# Adafruit_RS232_Pal.net
KiCad netlist of a schematic drawn in EAGLE
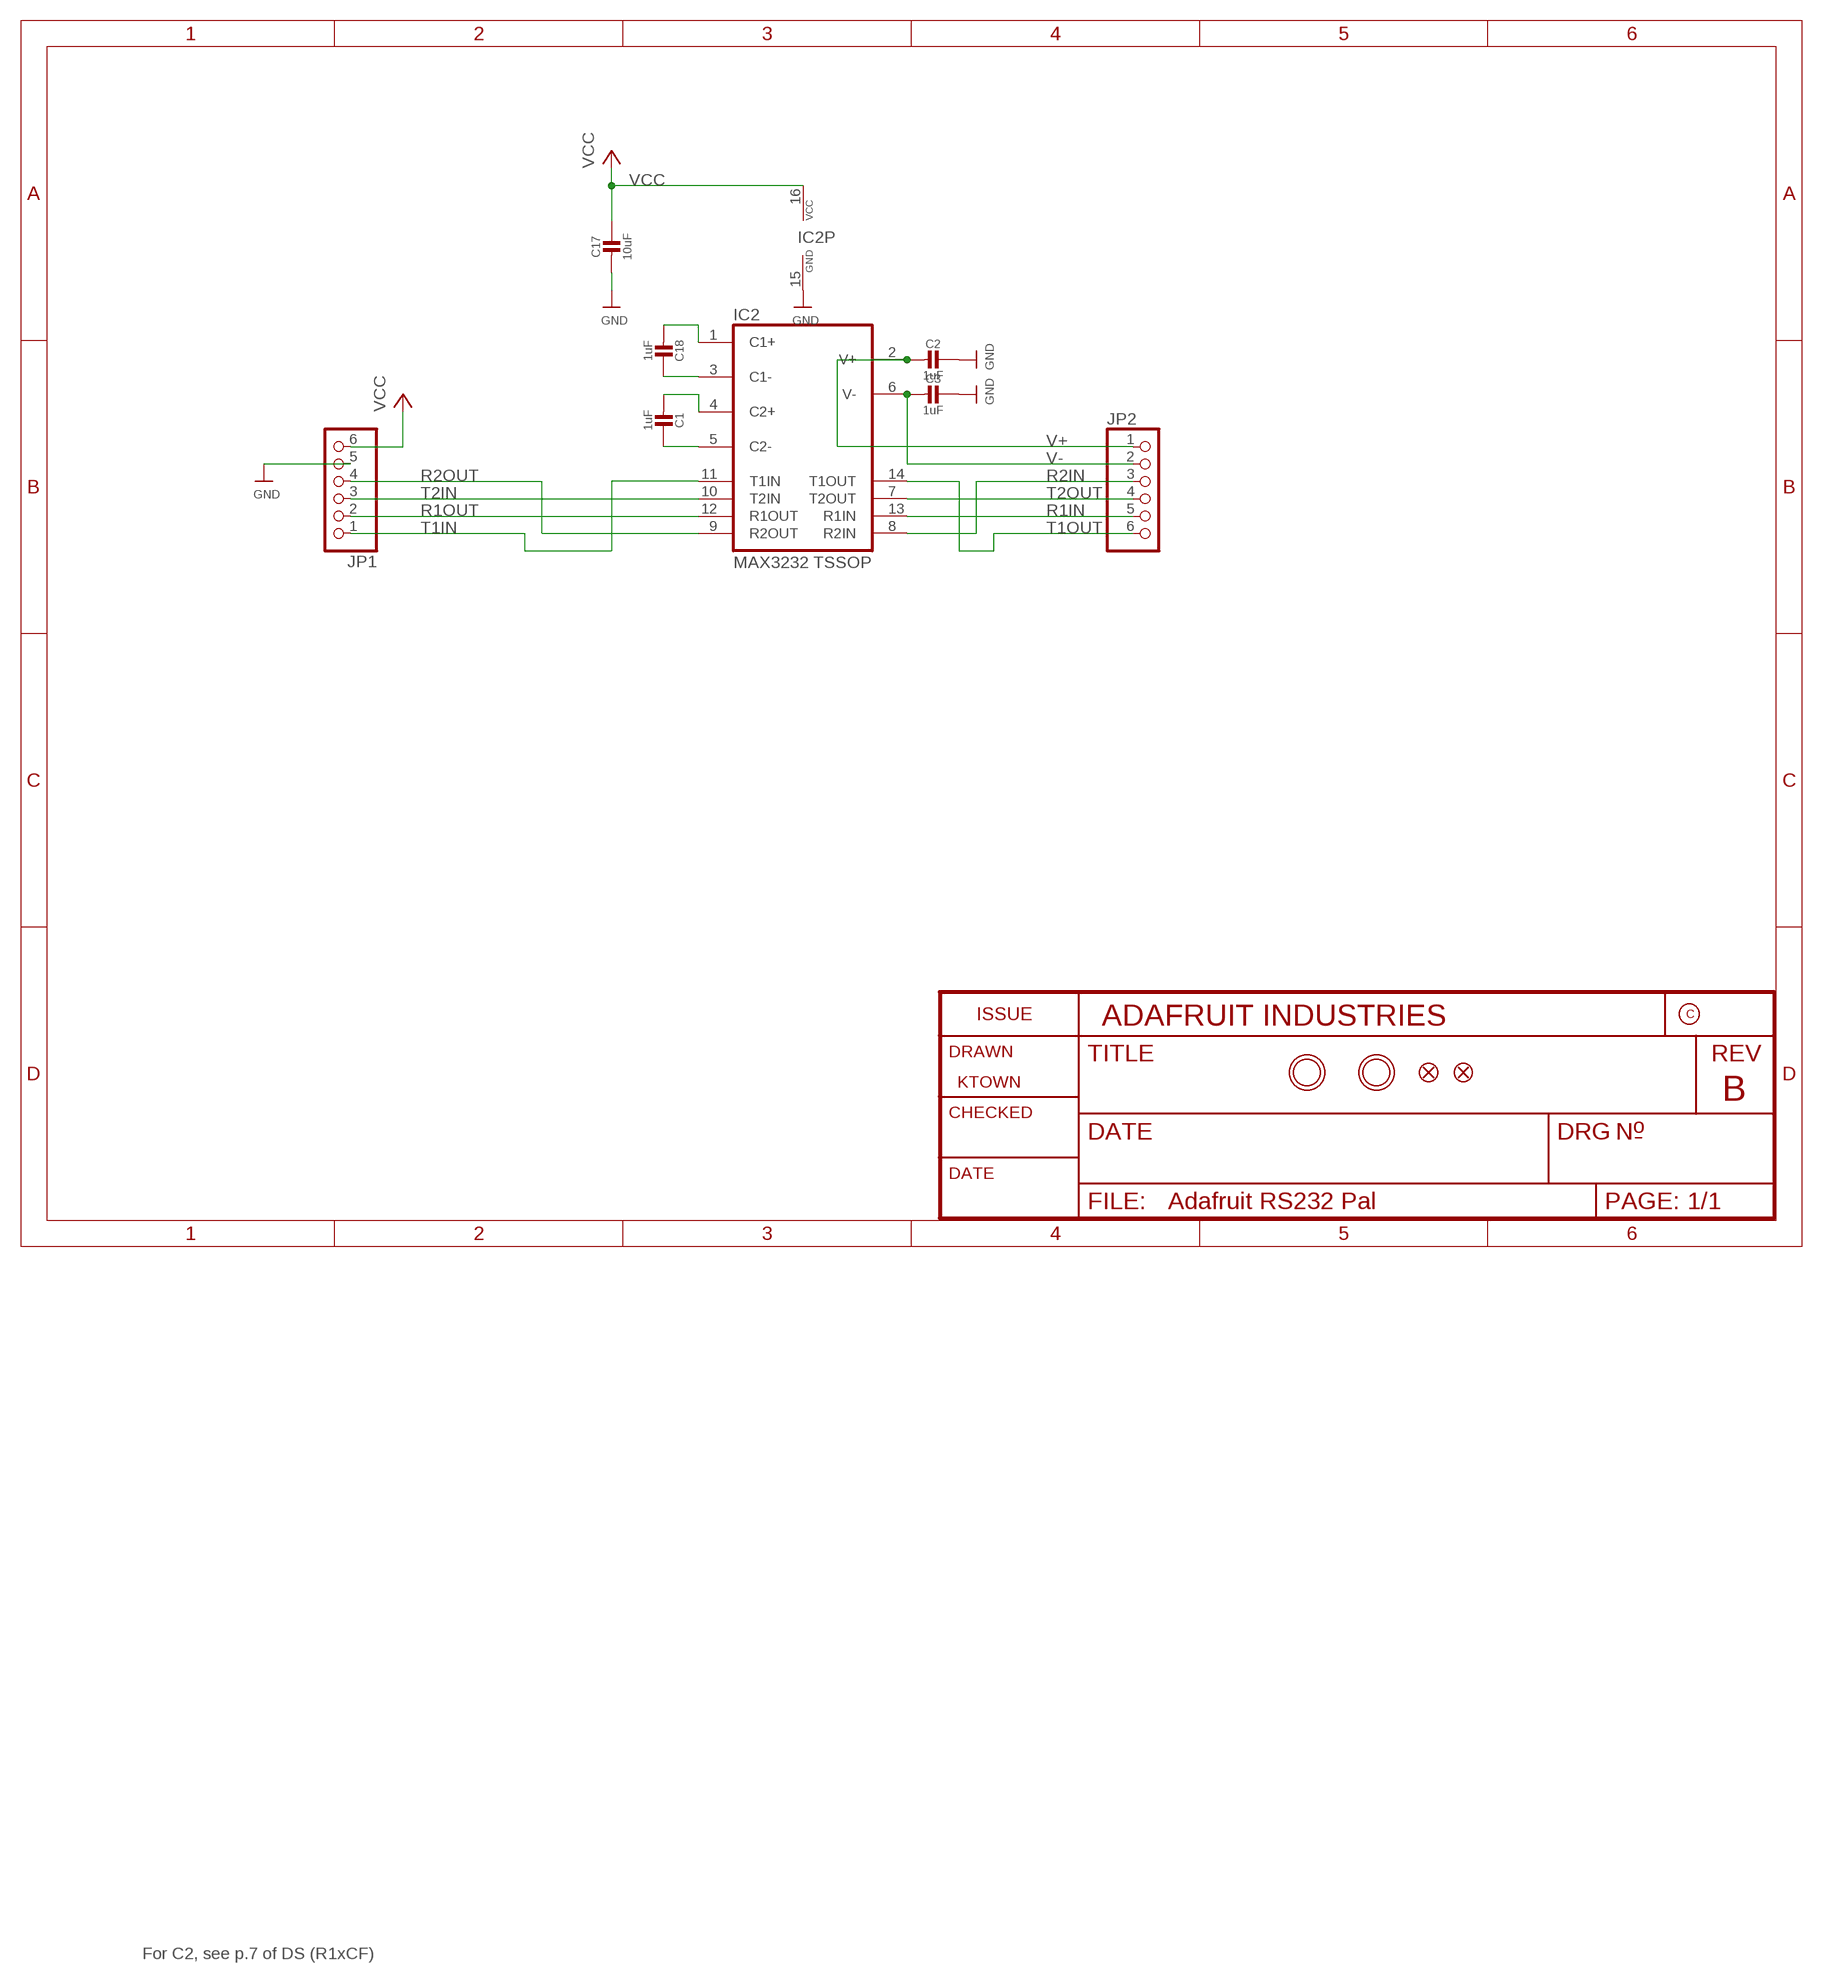
[diagram p0: schematic, sheet 1]

(export (version "E")
  (design (tool "Eeschema 10.0.6"))
  (components
    (comp (ref "C1")
      (value "1uF")
      (footprint "eagle-import:0603-NO")
      (libsource (lib "eagle-import") (part "CAP_CERAMIC0603_NO"))
    )
    (comp (ref "C2")
      (value "1uF")
      (footprint "eagle-import:0603-NO")
      (libsource (lib "eagle-import") (part "CAP_CERAMIC0603_NO"))
    )
    (comp (ref "C3")
      (value "1uF")
      (footprint "eagle-import:0603-NO")
      (libsource (lib "eagle-import") (part "CAP_CERAMIC0603_NO"))
    )
    (comp (ref "C17")
      (value "10uF")
      (footprint "eagle-import:0805-NO")
      (libsource (lib "eagle-import") (part "CAP_CERAMIC0805-NOOUTLINE"))
    )
    (comp (ref "C18")
      (value "1uF")
      (footprint "eagle-import:0603-NO")
      (libsource (lib "eagle-import") (part "CAP_CERAMIC0603_NO"))
    )
    (comp (ref "FID1")
      (value "FIDUCIAL_0.5MM")
      (footprint "eagle-import:FIDUCIAL_0.5MM")
      (libsource (lib "eagle-import") (part "FIDUCIAL_0.5MM"))
    )
    (comp (ref "FID2")
      (value "FIDUCIAL_0.5MM")
      (footprint "eagle-import:FIDUCIAL_0.5MM")
      (libsource (lib "eagle-import") (part "FIDUCIAL_0.5MM"))
    )
    (comp (ref "IC2")
      (value "MAX3232 TSSOP")
      (footprint "eagle-import:TSSOP16")
      (fields (field (name "MF") "MAXIM") (field (name "MPN") "MAX3232CUE+"))
      (libsource (lib "eagle-import") (part "MAX3232UEC"))
    )
    (comp (ref "JP1")
      (value "HEADER-1X670MIL")
      (footprint "eagle-import:1X06_ROUND_70")
      (libsource (lib "eagle-import") (part "HEADER-1X670MIL"))
    )
    (comp (ref "JP2")
      (value "HEADER-1X670MIL")
      (footprint "eagle-import:1X06_ROUND_70")
      (libsource (lib "eagle-import") (part "HEADER-1X670MIL"))
    )
    (comp (ref "U$2")
      (value "MOUNTINGHOLE2.5")
      (footprint "eagle-import:MOUNTINGHOLE_2.5_PLATED")
      (libsource (lib "eagle-import") (part "MOUNTINGHOLE2.5"))
    )
    (comp (ref "U$3")
      (value "MOUNTINGHOLE2.5")
      (footprint "eagle-import:MOUNTINGHOLE_2.5_PLATED")
      (libsource (lib "eagle-import") (part "MOUNTINGHOLE2.5"))
    )
  )
  (nets
    (net (code "1") (name "/R1IN") (class "Default")
      (node (ref "IC2") (pin "13") (pinfunction "R1IN_13") (pintype "input"))
      (node (ref "JP2") (pin "5") (pinfunction "5_5") (pintype "passive"))
    )
    (net (code "2") (name "/R1OUT") (class "Default")
      (node (ref "IC2") (pin "12") (pinfunction "R1OUT_12") (pintype "output"))
      (node (ref "JP1") (pin "2") (pinfunction "2_2") (pintype "passive"))
    )
    (net (code "3") (name "/R2IN") (class "Default")
      (node (ref "IC2") (pin "8") (pinfunction "R2IN_8") (pintype "input"))
      (node (ref "JP2") (pin "3") (pinfunction "3_3") (pintype "passive"))
    )
    (net (code "4") (name "/R2OUT") (class "Default")
      (node (ref "IC2") (pin "9") (pinfunction "R2OUT_9") (pintype "output"))
      (node (ref "JP1") (pin "4") (pinfunction "4_4") (pintype "passive"))
    )
    (net (code "5") (name "/T1IN") (class "Default")
      (node (ref "IC2") (pin "11") (pinfunction "T1IN_11") (pintype "input"))
      (node (ref "JP1") (pin "1") (pinfunction "1_1") (pintype "passive"))
    )
    (net (code "6") (name "/T1OUT") (class "Default")
      (node (ref "IC2") (pin "14") (pinfunction "T1OUT_14") (pintype "output"))
      (node (ref "JP2") (pin "6") (pinfunction "6_6") (pintype "passive"))
    )
    (net (code "7") (name "/T2IN") (class "Default")
      (node (ref "IC2") (pin "10") (pinfunction "T2IN_10") (pintype "input"))
      (node (ref "JP1") (pin "3") (pinfunction "3_3") (pintype "passive"))
    )
    (net (code "8") (name "/T2OUT") (class "Default")
      (node (ref "IC2") (pin "7") (pinfunction "T2OUT_7") (pintype "output"))
      (node (ref "JP2") (pin "4") (pinfunction "4_4") (pintype "passive"))
    )
    (net (code "9") (name "/V+") (class "Default")
      (node (ref "C2") (pin "2") (pinfunction "2_2") (pintype "passive"))
      (node (ref "IC2") (pin "2") (pinfunction "V+_2") (pintype "bidirectional"))
      (node (ref "JP2") (pin "1") (pinfunction "1_1") (pintype "passive"))
    )
    (net (code "10") (name "/V-") (class "Default")
      (node (ref "C3") (pin "2") (pinfunction "2_2") (pintype "passive"))
      (node (ref "IC2") (pin "6") (pinfunction "V-_6") (pintype "bidirectional"))
      (node (ref "JP2") (pin "2") (pinfunction "2_2") (pintype "passive"))
    )
    (net (code "11") (name "GND") (class "Default")
      (node (ref "C17") (pin "2") (pinfunction "2_2") (pintype "passive"))
      (node (ref "C2") (pin "1") (pinfunction "1_1") (pintype "passive"))
      (node (ref "C3") (pin "1") (pinfunction "1_1") (pintype "passive"))
      (node (ref "IC2") (pin "15") (pinfunction "GND_15") (pintype "power_in"))
      (node (ref "JP1") (pin "5") (pinfunction "5_5") (pintype "passive"))
    )
    (net (code "12") (name "Net-(IC2A-C1+)") (class "Default")
      (node (ref "C18") (pin "2") (pinfunction "2_2") (pintype "passive"))
      (node (ref "IC2") (pin "1") (pinfunction "C1+_1") (pintype "bidirectional"))
    )
    (net (code "13") (name "Net-(IC2A-C1-)") (class "Default")
      (node (ref "C18") (pin "1") (pinfunction "1_1") (pintype "passive"))
      (node (ref "IC2") (pin "3") (pinfunction "C1-_3") (pintype "bidirectional"))
    )
    (net (code "14") (name "Net-(IC2A-C2+)") (class "Default")
      (node (ref "C1") (pin "2") (pinfunction "2_2") (pintype "passive"))
      (node (ref "IC2") (pin "4") (pinfunction "C2+_4") (pintype "bidirectional"))
    )
    (net (code "15") (name "Net-(IC2A-C2-)") (class "Default")
      (node (ref "C1") (pin "1") (pinfunction "1_1") (pintype "passive"))
      (node (ref "IC2") (pin "5") (pinfunction "C2-_5") (pintype "bidirectional"))
    )
    (net (code "16") (name "VCC") (class "Default")
      (node (ref "C17") (pin "1") (pinfunction "1_1") (pintype "passive"))
      (node (ref "IC2") (pin "16") (pinfunction "VCC_16") (pintype "power_in"))
      (node (ref "JP1") (pin "6") (pinfunction "6_6") (pintype "passive"))
    )
  )
)
